# badge-seeed.net
KiCad netlist of a schematic drawn in EAGLE
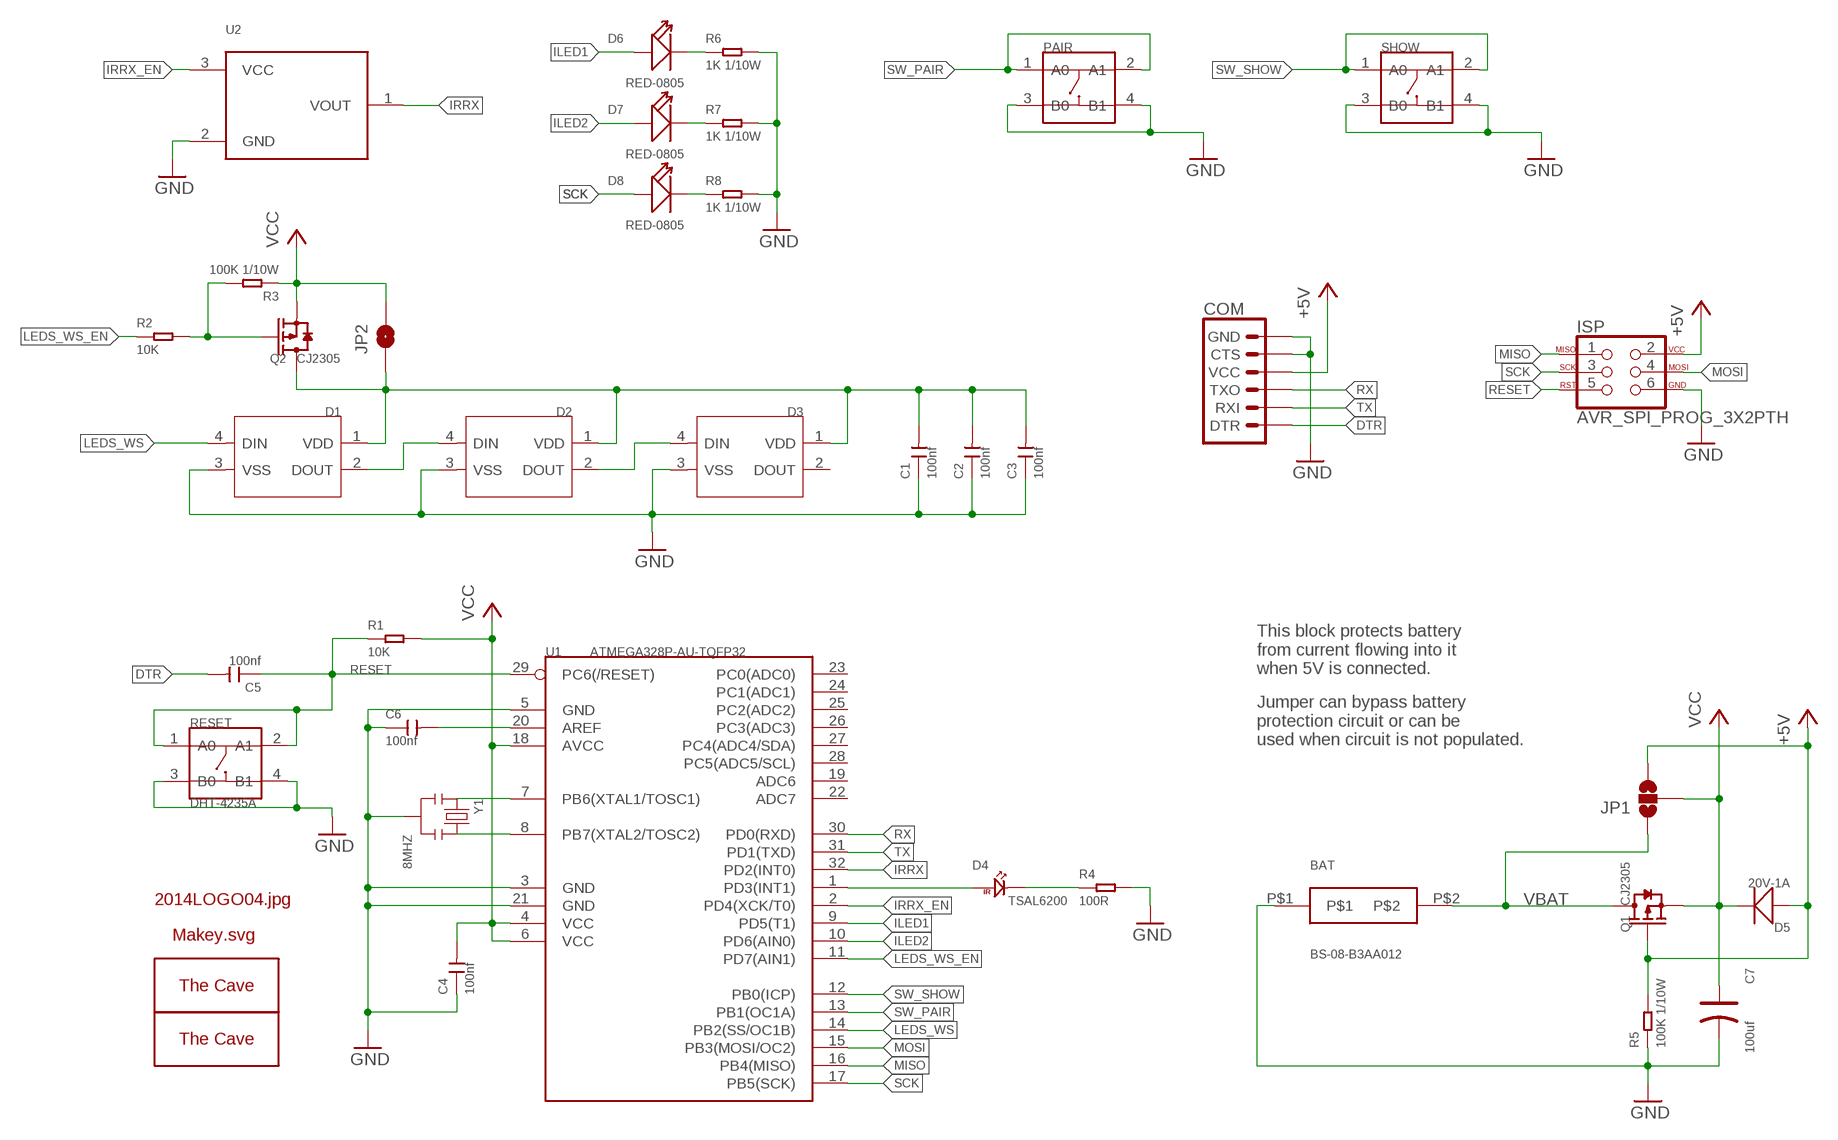
[diagram p0: schematic, sheet 1]

(export (version "E")
  (design (tool "Eeschema 10.0.6"))
  (components
    (comp (ref "BAT")
      (value "BS-08-B3AA012")
      (footprint "eagle-import:B3-08-B3AA012")
      (libsource (lib "eagle-import") (part "BS-08-B3AA012"))
    )
    (comp (ref "C1")
      (value "100nf")
      (footprint "eagle-import:C0603")
      (fields (field (name "MPN") "CC0603KRX7R9BB104"))
      (libsource (lib "eagle-import") (part "CERAMIC-100NF-50V-10%-X7R(0603)"))
    )
    (comp (ref "C2")
      (value "100nf")
      (footprint "eagle-import:C0603")
      (fields (field (name "MPN") "CC0603KRX7R9BB104"))
      (libsource (lib "eagle-import") (part "CERAMIC-100NF-50V-10%-X7R(0603)"))
    )
    (comp (ref "C3")
      (value "100nf")
      (footprint "eagle-import:C0603")
      (fields (field (name "MPN") "CC0603KRX7R9BB104"))
      (libsource (lib "eagle-import") (part "CERAMIC-100NF-50V-10%-X7R(0603)"))
    )
    (comp (ref "C4")
      (value "100nf")
      (footprint "eagle-import:C0603")
      (fields (field (name "MPN") "CC0603KRX7R9BB104"))
      (libsource (lib "eagle-import") (part "CERAMIC-100NF-50V-10%-X7R(0603)"))
    )
    (comp (ref "C5")
      (value "100nf")
      (footprint "eagle-import:C0603")
      (fields (field (name "MPN") "CC0603KRX7R9BB104"))
      (libsource (lib "eagle-import") (part "CERAMIC-100NF-50V-10%-X7R(0603)"))
    )
    (comp (ref "C6")
      (value "100nf")
      (footprint "eagle-import:C0603")
      (fields (field (name "MPN") "CC0603KRX7R9BB104"))
      (libsource (lib "eagle-import") (part "CERAMIC-100NF-50V-10%-X7R(0603)"))
    )
    (comp (ref "C7")
      (value "100uf")
      (footprint "eagle-import:AVX-B")
      (fields (field (name "MPN") "TAJB107M010#NJ"))
      (libsource (lib "eagle-import") (part "TANTALUM-SMD-100UF-10V(AVX-B)"))
    )
    (comp (ref "COM")
      (value "6_PIN_SERIAL_TARGETSILK")
      (footprint "eagle-import:6_PIN_SERIAL_TARGET_SIDE_W_SILK")
      (libsource (lib "eagle-import") (part "6_PIN_SERIAL_TARGETSILK"))
    )
    (comp (ref "D1")
      (value "SMD-RGB-LED-4P'WS2812B'")
      (footprint "eagle-import:LED4-SMD-5050")
      (libsource (lib "eagle-import") (part "SMD-RGB-LED-4P'WS2812B'"))
    )
    (comp (ref "D2")
      (value "SMD-RGB-LED-4P'WS2812B'")
      (footprint "eagle-import:LED4-SMD-5050")
      (libsource (lib "eagle-import") (part "SMD-RGB-LED-4P'WS2812B'"))
    )
    (comp (ref "D3")
      (value "SMD-RGB-LED-4P'WS2812B'")
      (footprint "eagle-import:LED4-SMD-5050")
      (libsource (lib "eagle-import") (part "SMD-RGB-LED-4P'WS2812B'"))
    )
    (comp (ref "D4")
      (value "TSAL6200")
      (footprint "eagle-import:TSAL6200")
      (libsource (lib "eagle-import") (part "TSAL6200"))
    )
    (comp (ref "D5")
      (value "20V-1A")
      (footprint "eagle-import:SOD-123")
      (fields (field (name "MPN") "B5819W"))
      (libsource (lib "eagle-import") (part "SMD-DIODE-SCHOTTKY-20V-1A(SOD-123)"))
    )
    (comp (ref "D6")
      (value "RED-0805")
      (footprint "eagle-import:LED-0805")
      (fields (field (name "MPN") "17-215SURC/S530-A2/TR8"))
      (libsource (lib "eagle-import") (part "SMD-LED-CLEAR-RED(0805)"))
    )
    (comp (ref "D7")
      (value "RED-0805")
      (footprint "eagle-import:LED-0805")
      (fields (field (name "MPN") "17-215SURC/S530-A2/TR8"))
      (libsource (lib "eagle-import") (part "SMD-LED-CLEAR-RED(0805)"))
    )
    (comp (ref "D8")
      (value "RED-0805")
      (footprint "eagle-import:LED-0805")
      (fields (field (name "MPN") "17-215SURC/S530-A2/TR8"))
      (libsource (lib "eagle-import") (part "SMD-LED-CLEAR-RED(0805)"))
    )
    (comp (ref "ISP")
      (value "AVR_SPI_PROG_3X2PTH")
      (footprint "eagle-import:2X3")
      (libsource (lib "eagle-import") (part "AVR_SPI_PROG_3X2PTH"))
    )
    (comp (ref "JP1")
      (value "JUMPER-SMT_3_NO_SILK")
      (footprint "eagle-import:SMT-JUMPER_3_NO_SILK")
      (libsource (lib "eagle-import") (part "JUMPER-SMT_3_NO_SILK"))
    )
    (comp (ref "JP2")
      (value "JUMPER-SMT_2_NO_SILK")
      (footprint "eagle-import:SMT-JUMPER_2_NO_SILK")
      (libsource (lib "eagle-import") (part "JUMPER-SMT_2_NO_SILK"))
    )
    (comp (ref "PAIR")
      (value "SMD-BUTTON(4P-5.2X5.2X1.5MM-SKQGADE010)-SKQGADE010")
      (footprint "eagle-import:SW4-SMD-5.2X5.2X1.5MM")
      (fields (field (name "MPN") "SKQGADE010"))
      (libsource (lib "eagle-import") (part "SMD-BUTTON(4P-5.2X5.2X1.5MM-SKQGADE010)-SKQGADE010"))
    )
    (comp (ref "Q1")
      (value "CJ2305")
      (footprint "eagle-import:SOT-23")
      (libsource (lib "eagle-import") (part "SMD-MOSFET-P-CH-8V-4.1A-CJ2305(SOT-23)"))
    )
    (comp (ref "Q2")
      (value "CJ2305")
      (footprint "eagle-import:SOT-23")
      (libsource (lib "eagle-import") (part "SMD-MOSFET-P-CH-8V-4.1A-CJ2305(SOT-23)"))
    )
    (comp (ref "R1")
      (value "10K")
      (footprint "eagle-import:R0603")
      (fields (field (name "MPN") "RC0603FR-0710KL"))
      (libsource (lib "eagle-import") (part "SMD-RES-10K-1%-1/10W(0603)"))
    )
    (comp (ref "R2")
      (value "10K")
      (footprint "eagle-import:R0603")
      (fields (field (name "MPN") "RC0603FR-0710KL"))
      (libsource (lib "eagle-import") (part "SMD-RES-10K-1%-1/10W(0603)"))
    )
    (comp (ref "R3")
      (value "100K 1/10W")
      (footprint "eagle-import:R0603")
      (fields (field (name "MPN") "RC0603JR-07100KL"))
      (libsource (lib "eagle-import") (part "SMD-RES-100K-5%-1/10W(0603)"))
    )
    (comp (ref "R4")
      (value "100R")
      (footprint "eagle-import:R0805")
      (fields (field (name "MPN") "RC0805JR-07100RL"))
      (libsource (lib "eagle-import") (part "SMD-RES-100R-5%-1/8W(0805)"))
    )
    (comp (ref "R5")
      (value "100K 1/10W")
      (footprint "eagle-import:R0603")
      (fields (field (name "MPN") "RC0603JR-07100KL"))
      (libsource (lib "eagle-import") (part "SMD-RES-100K-5%-1/10W(0603)"))
    )
    (comp (ref "R6")
      (value "1K 1/10W")
      (footprint "eagle-import:R0603")
      (fields (field (name "MPN") "RC0603JR-071KL"))
      (libsource (lib "eagle-import") (part "SMD-RES-1K-5%-1/10W(0603)"))
    )
    (comp (ref "R7")
      (value "1K 1/10W")
      (footprint "eagle-import:R0603")
      (fields (field (name "MPN") "RC0603JR-071KL"))
      (libsource (lib "eagle-import") (part "SMD-RES-1K-5%-1/10W(0603)"))
    )
    (comp (ref "R8")
      (value "1K 1/10W")
      (footprint "eagle-import:R0603")
      (fields (field (name "MPN") "RC0603JR-071KL"))
      (libsource (lib "eagle-import") (part "SMD-RES-1K-5%-1/10W(0603)"))
    )
    (comp (ref "RESET")
      (value "DHT-4235A")
      (footprint "eagle-import:SW4-SMD-4.2X3.2X2.5MM")
      (libsource (lib "eagle-import") (part "SMD-BUTTON-TOP-DHT-4235A(4P-4.2X3.2MM)"))
    )
    (comp (ref "SHOW")
      (value "SMD-BUTTON(4P-5.2X5.2X1.5MM-SKQGADE010)-SKQGADE010")
      (footprint "eagle-import:SW4-SMD-5.2X5.2X1.5MM")
      (fields (field (name "MPN") "SKQGADE010"))
      (libsource (lib "eagle-import") (part "SMD-BUTTON(4P-5.2X5.2X1.5MM-SKQGADE010)-SKQGADE010"))
    )
    (comp (ref "U$1")
      (value "2014LOGO04#JPG")
      (footprint "eagle-import:2014LOGO04#JPG")
      (libsource (lib "eagle-import") (part "2014LOGO04#JPG"))
    )
    (comp (ref "U$2")
      (value "MAKEY#SVG")
      (footprint "eagle-import:MAKEY#SVG")
      (libsource (lib "eagle-import") (part "MAKEY#SVG"))
    )
    (comp (ref "U$3")
      (value "THECAVE_LOGO_TOP_SMALL")
      (footprint "eagle-import:LOGO_TOP_SMALL")
      (libsource (lib "eagle-import") (part "THECAVE_LOGO_TOP_SMALL"))
    )
    (comp (ref "U$4")
      (value "THECAVE_LOGO_COPPER_TEXT")
      (footprint "eagle-import:LOGO_COPPER_TEXT")
      (libsource (lib "eagle-import") (part "THECAVE_LOGO_COPPER_TEXT"))
    )
    (comp (ref "U1")
      (value "ATMEGA328P-AU-TQFP32")
      (footprint "eagle-import:TQFP32-0.8-7X7MM")
      (fields (field (name "MPN") "ATMEGA328P-AU"))
      (libsource (lib "eagle-import") (part "MCU-ATMEGA328P-AU(TQFP32)"))
    )
    (comp (ref "U2")
      (value "TSOP382")
      (footprint "eagle-import:TSOP382")
      (libsource (lib "eagle-import") (part "TSOP382"))
    )
    (comp (ref "Y1")
      (value "8MHZ")
      (footprint "eagle-import:X3-SMD-3.6X1.3X0.8MM")
      (libsource (lib "eagle-import") (part "SMD-CRYSTAL-8MHZ--0.3%-150R(3P-3.6X1.3MM)"))
    )
  )
  (nets
    (net (code "1") (name "+5V") (class "Default")
      (node (ref "COM") (pin "P$4") (pinfunction "VCC_P$4") (pintype "passive"))
      (node (ref "D5") (pin "+") (pinfunction "+_+") (pintype "passive"))
      (node (ref "ISP") (pin "2") (pinfunction "2_2") (pintype "passive"))
      (node (ref "JP1") (pin "3") (pinfunction "3_3") (pintype "passive"))
      (node (ref "Q1") (pin "1") (pinfunction "G_1") (pintype "passive"))
      (node (ref "R5") (pin "2") (pinfunction "2_2") (pintype "passive"))
    )
    (net (code "2") (name "/VBAT") (class "Default")
      (node (ref "BAT") (pin "P$2") (pinfunction "P$2_P$2") (pintype "bidirectional"))
      (node (ref "JP1") (pin "1") (pinfunction "1_1") (pintype "passive"))
      (node (ref "Q1") (pin "3") (pinfunction "D_3") (pintype "passive"))
    )
    (net (code "3") (name "DTR") (class "Default")
      (node (ref "C5") (pin "2") (pinfunction "2_2") (pintype "passive"))
      (node (ref "COM") (pin "P$1") (pinfunction "DTR_P$1") (pintype "passive"))
    )
    (net (code "4") (name "GND") (class "Default")
      (node (ref "BAT") (pin "P$1") (pinfunction "P$1_P$1") (pintype "bidirectional"))
      (node (ref "C1") (pin "1") (pinfunction "1_1") (pintype "passive"))
      (node (ref "C2") (pin "1") (pinfunction "1_1") (pintype "passive"))
      (node (ref "C3") (pin "1") (pinfunction "1_1") (pintype "passive"))
      (node (ref "C4") (pin "1") (pinfunction "1_1") (pintype "passive"))
      (node (ref "C6") (pin "1") (pinfunction "1_1") (pintype "passive"))
      (node (ref "C7") (pin "-") (pinfunction "-_-") (pintype "passive"))
      (node (ref "COM") (pin "P$5") (pinfunction "CTS_P$5") (pintype "passive"))
      (node (ref "COM") (pin "P$6") (pinfunction "GND_P$6") (pintype "passive"))
      (node (ref "D1") (pin "3") (pinfunction "VSS_3") (pintype "bidirectional"))
      (node (ref "D2") (pin "3") (pinfunction "VSS_3") (pintype "bidirectional"))
      (node (ref "D3") (pin "3") (pinfunction "VSS_3") (pintype "bidirectional"))
      (node (ref "ISP") (pin "6") (pinfunction "6_6") (pintype "passive"))
      (node (ref "PAIR") (pin "3") (pinfunction "B0_3") (pintype "bidirectional"))
      (node (ref "PAIR") (pin "4") (pinfunction "B1_4") (pintype "bidirectional"))
      (node (ref "R4") (pin "2") (pinfunction "2_2") (pintype "passive"))
      (node (ref "R5") (pin "1") (pinfunction "1_1") (pintype "passive"))
      (node (ref "R6") (pin "2") (pinfunction "2_2") (pintype "passive"))
      (node (ref "R7") (pin "2") (pinfunction "2_2") (pintype "passive"))
      (node (ref "R8") (pin "2") (pinfunction "2_2") (pintype "passive"))
      (node (ref "RESET") (pin "3") (pinfunction "B0_3") (pintype "bidirectional"))
      (node (ref "RESET") (pin "4") (pinfunction "B1_4") (pintype "bidirectional"))
      (node (ref "SHOW") (pin "3") (pinfunction "B0_3") (pintype "bidirectional"))
      (node (ref "SHOW") (pin "4") (pinfunction "B1_4") (pintype "bidirectional"))
      (node (ref "U1") (pin "21") (pinfunction "GND_21") (pintype "bidirectional"))
      (node (ref "U1") (pin "3") (pinfunction "GND_3") (pintype "bidirectional"))
      (node (ref "U1") (pin "5") (pinfunction "GND_5") (pintype "bidirectional"))
      (node (ref "U2") (pin "2") (pinfunction "GND_2") (pintype "bidirectional"))
      (node (ref "Y1") (pin "2") (pinfunction "2_2") (pintype "passive"))
    )
    (net (code "5") (name "ILED1") (class "Default")
      (node (ref "D6") (pin "+") (pinfunction "+_+") (pintype "passive"))
      (node (ref "U1") (pin "9") (pinfunction "PD5(T1)_9") (pintype "bidirectional"))
    )
    (net (code "6") (name "ILED2") (class "Default")
      (node (ref "D7") (pin "+") (pinfunction "+_+") (pintype "passive"))
      (node (ref "U1") (pin "10") (pinfunction "PD6(AIN0)_10") (pintype "bidirectional"))
    )
    (net (code "7") (name "IRRX") (class "Default")
      (node (ref "U1") (pin "32") (pinfunction "PD2(INT0)_32") (pintype "bidirectional"))
      (node (ref "U2") (pin "1") (pinfunction "VOUT_1") (pintype "bidirectional"))
    )
    (net (code "8") (name "IRRX_EN") (class "Default")
      (node (ref "U1") (pin "2") (pinfunction "PD4(XCK/T0)_2") (pintype "bidirectional"))
      (node (ref "U2") (pin "3") (pinfunction "VCC_3") (pintype "bidirectional"))
    )
    (net (code "9") (name "LEDS_WS") (class "Default")
      (node (ref "D1") (pin "4") (pinfunction "DIN_4") (pintype "bidirectional"))
      (node (ref "U1") (pin "14") (pinfunction "PB2(SS/OC1B)_14") (pintype "bidirectional"))
    )
    (net (code "10") (name "LEDS_WS_EN") (class "Default")
      (node (ref "R2") (pin "1") (pinfunction "1_1") (pintype "passive"))
      (node (ref "U1") (pin "11") (pinfunction "PD7(AIN1)_11") (pintype "bidirectional"))
    )
    (net (code "11") (name "MISO") (class "Default")
      (node (ref "ISP") (pin "1") (pinfunction "1_1") (pintype "passive"))
      (node (ref "U1") (pin "16") (pinfunction "PB4(MISO)_16") (pintype "bidirectional"))
    )
    (net (code "12") (name "MOSI") (class "Default")
      (node (ref "ISP") (pin "4") (pinfunction "4_4") (pintype "passive"))
      (node (ref "U1") (pin "15") (pinfunction "PB3(MOSI/OC2)_15") (pintype "bidirectional"))
    )
    (net (code "13") (name "Net-(D1-DOUT)") (class "Default")
      (node (ref "D1") (pin "2") (pinfunction "DOUT_2") (pintype "bidirectional"))
      (node (ref "D2") (pin "4") (pinfunction "DIN_4") (pintype "bidirectional"))
    )
    (net (code "14") (name "Net-(D1-VDD)") (class "Default")
      (node (ref "C1") (pin "2") (pinfunction "2_2") (pintype "passive"))
      (node (ref "C2") (pin "2") (pinfunction "2_2") (pintype "passive"))
      (node (ref "C3") (pin "2") (pinfunction "2_2") (pintype "passive"))
      (node (ref "D1") (pin "1") (pinfunction "VDD_1") (pintype "bidirectional"))
      (node (ref "D2") (pin "1") (pinfunction "VDD_1") (pintype "bidirectional"))
      (node (ref "D3") (pin "1") (pinfunction "VDD_1") (pintype "bidirectional"))
      (node (ref "JP2") (pin "1") (pinfunction "1_1") (pintype "passive"))
      (node (ref "Q2") (pin "3") (pinfunction "D_3") (pintype "passive"))
    )
    (net (code "15") (name "Net-(D2-DOUT)") (class "Default")
      (node (ref "D2") (pin "2") (pinfunction "DOUT_2") (pintype "bidirectional"))
      (node (ref "D3") (pin "4") (pinfunction "DIN_4") (pintype "bidirectional"))
    )
    (net (code "16") (name "Net-(D4-PadN)") (class "Default")
      (node (ref "D4") (pin "N") (pinfunction "N_N") (pintype "bidirectional"))
      (node (ref "R4") (pin "1") (pinfunction "1_1") (pintype "passive"))
    )
    (net (code "17") (name "Net-(D6-Pad-)") (class "Default")
      (node (ref "D6") (pin "-") (pinfunction "-_-") (pintype "passive"))
      (node (ref "R6") (pin "1") (pinfunction "1_1") (pintype "passive"))
    )
    (net (code "18") (name "Net-(D7-Pad-)") (class "Default")
      (node (ref "D7") (pin "-") (pinfunction "-_-") (pintype "passive"))
      (node (ref "R7") (pin "1") (pinfunction "1_1") (pintype "passive"))
    )
    (net (code "19") (name "Net-(D8-Pad-)") (class "Default")
      (node (ref "D8") (pin "-") (pinfunction "-_-") (pintype "passive"))
      (node (ref "R8") (pin "1") (pinfunction "1_1") (pintype "passive"))
    )
    (net (code "20") (name "Net-(Q2-G)") (class "Default")
      (node (ref "Q2") (pin "1") (pinfunction "G_1") (pintype "passive"))
      (node (ref "R2") (pin "2") (pinfunction "2_2") (pintype "passive"))
      (node (ref "R3") (pin "2") (pinfunction "2_2") (pintype "passive"))
    )
    (net (code "21") (name "Net-(U1-AREF)") (class "Default")
      (node (ref "C6") (pin "2") (pinfunction "2_2") (pintype "passive"))
      (node (ref "U1") (pin "20") (pinfunction "AREF_20") (pintype "bidirectional"))
    )
    (net (code "22") (name "Net-(U1-PB6(XTAL1{slash}TOSC1))") (class "Default")
      (node (ref "U1") (pin "7") (pinfunction "PB6(XTAL1/TOSC1)_7") (pintype "bidirectional"))
      (node (ref "Y1") (pin "1") (pinfunction "1_1") (pintype "passive"))
    )
    (net (code "23") (name "Net-(U1-PB7(XTAL2{slash}TOSC2))") (class "Default")
      (node (ref "U1") (pin "8") (pinfunction "PB7(XTAL2/TOSC2)_8") (pintype "bidirectional"))
      (node (ref "Y1") (pin "3") (pinfunction "3_3") (pintype "passive"))
    )
    (net (code "24") (name "Net-(U1-PD3(INT1))") (class "Default")
      (node (ref "D4") (pin "P") (pinfunction "P_P") (pintype "bidirectional"))
      (node (ref "U1") (pin "1") (pinfunction "PD3(INT1)_1") (pintype "bidirectional"))
    )
    (net (code "25") (name "RESET") (class "Default")
      (node (ref "C5") (pin "1") (pinfunction "1_1") (pintype "passive"))
      (node (ref "ISP") (pin "5") (pinfunction "5_5") (pintype "passive"))
      (node (ref "R1") (pin "1") (pinfunction "1_1") (pintype "passive"))
      (node (ref "RESET") (pin "1") (pinfunction "A0_1") (pintype "bidirectional"))
      (node (ref "RESET") (pin "2") (pinfunction "A1_2") (pintype "bidirectional"))
      (node (ref "U1") (pin "29") (pinfunction "PC6(/RESET)_29") (pintype "bidirectional"))
    )
    (net (code "26") (name "RX") (class "Default")
      (node (ref "COM") (pin "P$2") (pinfunction "TXO_P$2") (pintype "passive"))
      (node (ref "U1") (pin "30") (pinfunction "PD0(RXD)_30") (pintype "bidirectional"))
    )
    (net (code "27") (name "SCK") (class "Default")
      (node (ref "D8") (pin "+") (pinfunction "+_+") (pintype "passive"))
      (node (ref "ISP") (pin "3") (pinfunction "3_3") (pintype "passive"))
      (node (ref "U1") (pin "17") (pinfunction "PB5(SCK)_17") (pintype "bidirectional"))
    )
    (net (code "28") (name "SW_PAIR") (class "Default")
      (node (ref "PAIR") (pin "1") (pinfunction "A0_1") (pintype "bidirectional"))
      (node (ref "PAIR") (pin "2") (pinfunction "A1_2") (pintype "bidirectional"))
      (node (ref "U1") (pin "13") (pinfunction "PB1(OC1A)_13") (pintype "bidirectional"))
    )
    (net (code "29") (name "SW_SHOW") (class "Default")
      (node (ref "SHOW") (pin "1") (pinfunction "A0_1") (pintype "bidirectional"))
      (node (ref "SHOW") (pin "2") (pinfunction "A1_2") (pintype "bidirectional"))
      (node (ref "U1") (pin "12") (pinfunction "PB0(ICP)_12") (pintype "bidirectional"))
    )
    (net (code "30") (name "TX") (class "Default")
      (node (ref "COM") (pin "P$3") (pinfunction "RXI_P$3") (pintype "passive"))
      (node (ref "U1") (pin "31") (pinfunction "PD1(TXD)_31") (pintype "bidirectional"))
    )
    (net (code "31") (name "VCC") (class "Default")
      (node (ref "C4") (pin "2") (pinfunction "2_2") (pintype "passive"))
      (node (ref "C7") (pin "+") (pinfunction "+_+") (pintype "passive"))
      (node (ref "D5") (pin "-") (pinfunction "-_-") (pintype "passive"))
      (node (ref "JP1") (pin "2") (pinfunction "2_2") (pintype "passive"))
      (node (ref "JP2") (pin "2") (pinfunction "2_2") (pintype "passive"))
      (node (ref "Q1") (pin "2") (pinfunction "S_2") (pintype "passive"))
      (node (ref "Q2") (pin "2") (pinfunction "S_2") (pintype "passive"))
      (node (ref "R1") (pin "2") (pinfunction "2_2") (pintype "passive"))
      (node (ref "R3") (pin "1") (pinfunction "1_1") (pintype "passive"))
      (node (ref "U1") (pin "18") (pinfunction "AVCC_18") (pintype "bidirectional"))
      (node (ref "U1") (pin "4") (pinfunction "VCC_4") (pintype "bidirectional"))
      (node (ref "U1") (pin "6") (pinfunction "VCC_6") (pintype "bidirectional"))
    )
    (net (code "32") (name "unconnected-(D3-DOUT-Pad2)") (class "Default")
      (node (ref "D3") (pin "2") (pinfunction "DOUT_2") (pintype "bidirectional"))
    )
    (net (code "33") (name "unconnected-(U1-ADC6-Pad19)") (class "Default")
      (node (ref "U1") (pin "19") (pinfunction "ADC6_19") (pintype "bidirectional"))
    )
    (net (code "34") (name "unconnected-(U1-ADC7-Pad22)") (class "Default")
      (node (ref "U1") (pin "22") (pinfunction "ADC7_22") (pintype "bidirectional"))
    )
    (net (code "35") (name "unconnected-(U1-PC0(ADC0)-Pad23)") (class "Default")
      (node (ref "U1") (pin "23") (pinfunction "PC0(ADC0)_23") (pintype "bidirectional"))
    )
    (net (code "36") (name "unconnected-(U1-PC1(ADC1)-Pad24)") (class "Default")
      (node (ref "U1") (pin "24") (pinfunction "PC1(ADC1)_24") (pintype "bidirectional"))
    )
    (net (code "37") (name "unconnected-(U1-PC2(ADC2)-Pad25)") (class "Default")
      (node (ref "U1") (pin "25") (pinfunction "PC2(ADC2)_25") (pintype "bidirectional"))
    )
    (net (code "38") (name "unconnected-(U1-PC3(ADC3)-Pad26)") (class "Default")
      (node (ref "U1") (pin "26") (pinfunction "PC3(ADC3)_26") (pintype "bidirectional"))
    )
    (net (code "39") (name "unconnected-(U1-PC4(ADC4{slash}SDA)-Pad27)") (class "Default")
      (node (ref "U1") (pin "27") (pinfunction "PC4(ADC4/SDA)_27") (pintype "bidirectional"))
    )
    (net (code "40") (name "unconnected-(U1-PC5(ADC5{slash}SCL)-Pad28)") (class "Default")
      (node (ref "U1") (pin "28") (pinfunction "PC5(ADC5/SCL)_28") (pintype "bidirectional"))
    )
  )
)
